# LSWM_00_HCMS29_Lithium.net
KiCad netlist of a schematic drawn in Altium Designer
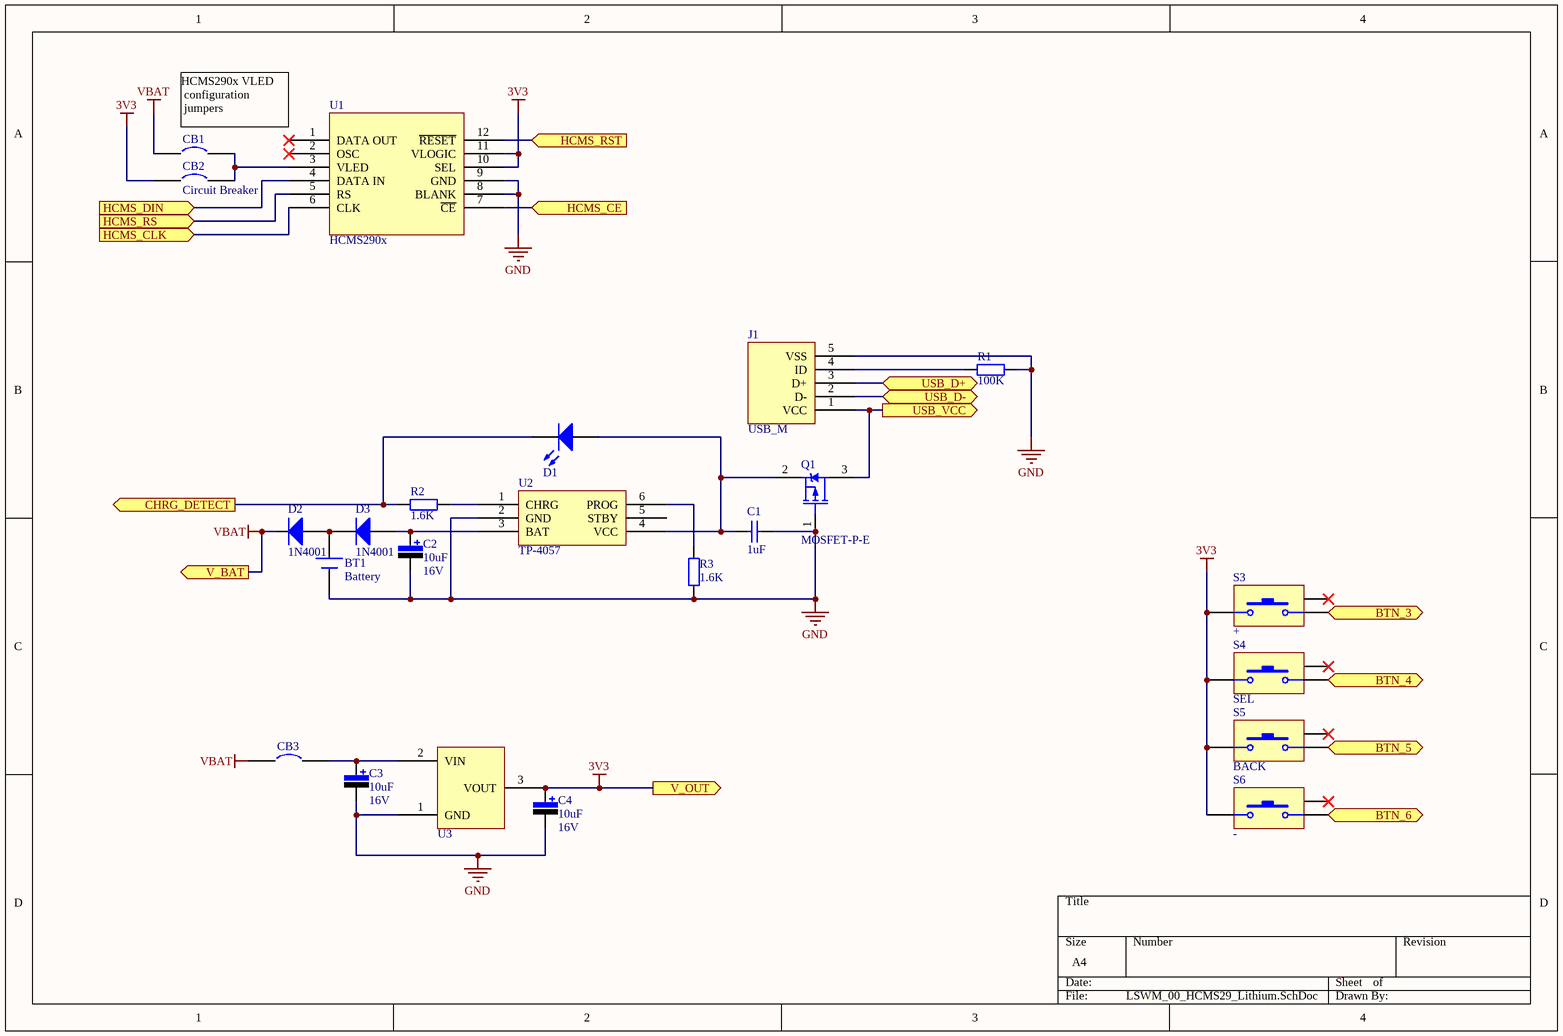
[diagram p0: LSWM_00_HCMS29_Lithium.SchDoc]

(export (version "E")
  (design (tool "Eeschema 10.0.6"))
  (components
    (comp (ref "BT1")
      (value "Battery")
      (footprint "HDR2X1_A")
      (description "备份电池")
      (fields (field (name "PUBLISHER") "Altium Limited"))
      (libsource (lib "Schlib1") (part "Battery_1"))
    )
    (comp (ref "C1")
      (value "1uF")
      (footprint "0805-1")
      (description "无极性电容")
      (fields (field (name "Comment") "Cap") (field (name "PUBLISHER") "Altium Limited"))
      (libsource (lib "fszhang") (part "Cap"))
    )
    (comp (ref "C2")
      (value "10uF")
      (footprint "1206-POL")
      (description "极性电解电容")
      (fields
        (field (name "VOL") "16V")
        (field (name "Comment") "Cap Pol")
        (field (name "PUBLISHER") "Altium Limited")
      )
      (libsource (lib "fszhang") (part "Cap Pol"))
    )
    (comp (ref "C3")
      (value "10uF")
      (footprint "1206-POL")
      (description "极性电解电容")
      (fields
        (field (name "VOL") "16V")
        (field (name "Comment") "Cap Pol")
        (field (name "PUBLISHER") "Altium Limited")
      )
      (libsource (lib "fszhang") (part "Cap Pol"))
    )
    (comp (ref "C4")
      (value "10uF")
      (footprint "1206-POL")
      (description "极性电解电容")
      (fields
        (field (name "VOL") "16V")
        (field (name "Comment") "Cap Pol")
        (field (name "PUBLISHER") "Altium Limited")
      )
      (libsource (lib "fszhang") (part "Cap Pol"))
    )
    (comp (ref "CB1")
      (value "Circuit Breaker")
      (footprint "SB-0805")
      (fields (field (name "PUBLISHER") "Altium Limited"))
      (libsource (lib "Schlib1") (part "Circuit Breaker"))
    )
    (comp (ref "CB2")
      (value "Circuit Breaker")
      (footprint "SB-0805")
      (fields (field (name "PUBLISHER") "Altium Limited"))
      (libsource (lib "Schlib1") (part "Circuit Breaker"))
    )
    (comp (ref "CB3")
      (value "Circuit Breaker")
      (footprint "SB-0805")
      (fields (field (name "PUBLISHER") "Altium Limited"))
      (libsource (lib "Schlib1") (part "Circuit Breaker"))
    )
    (comp (ref "D1")
      (value "LED0")
      (footprint "LED_0805")
      (description "发光二极管")
      (fields (field (name "PUBLISHER") "Altium Limited"))
      (libsource (lib "fszhang") (part "LED0"))
    )
    (comp (ref "D2")
      (value "Diode")
      (footprint "SOD323")
      (description "二极管")
      (fields (field (name "TYPE") "1N4001") (field (name "PUBLISHER") "Altium Limited"))
      (libsource (lib "fszhang") (part "Diode"))
    )
    (comp (ref "D3")
      (value "Diode")
      (footprint "SOD323")
      (description "二极管")
      (fields (field (name "TYPE") "1N4001") (field (name "PUBLISHER") "Altium Limited"))
      (libsource (lib "fszhang") (part "Diode"))
    )
    (comp (ref "J1")
      (value "USB_M")
      (footprint "USB_MICRO")
      (description "MicroUSB接口")
      (libsource (lib "fszhang") (part "USB_M"))
    )
    (comp (ref "Q1")
      (value "MOSFET-P-E")
      (footprint "SOT-23")
      (description "P-Channel Enhanced MOSFET")
      (fields (field (name "PUBLISHER") "Altium Limited"))
      (libsource (lib "Schlib1") (part "MOSFET-P-E"))
    )
    (comp (ref "R1")
      (value "100K")
      (footprint "0603-1")
      (description "贴片电阻")
      (fields (field (name "Comment") "Res1") (field (name "PUBLISHER") "Altium Limited"))
      (libsource (lib "fszhang") (part "Res1"))
    )
    (comp (ref "R2")
      (value "1.6K")
      (footprint "0603-1")
      (description "贴片电阻")
      (fields (field (name "Comment") "Res1") (field (name "PUBLISHER") "Altium Limited"))
      (libsource (lib "") (part "Res1_2"))
    )
    (comp (ref "R3")
      (value "1.6K")
      (footprint "0805-1")
      (description "贴片电阻")
      (fields (field (name "Comment") "Res1") (field (name "PUBLISHER") "Altium Limited"))
      (libsource (lib "") (part "Res1_1"))
    )
    (comp (ref "S3")
      (value "+")
      (footprint "BTN_2_4_35")
      (description "微动开关")
      (fields (field (name "PUBLISHER") "Altium Limited"))
      (libsource (lib "Schlib1") (part "SW-PB"))
    )
    (comp (ref "S4")
      (value "SEL")
      (footprint "BTN_2_4_35")
      (description "微动开关")
      (fields (field (name "PUBLISHER") "Altium Limited"))
      (libsource (lib "Schlib1") (part "SW-PB"))
    )
    (comp (ref "S5")
      (value "BACK")
      (footprint "BTN_2_4_35")
      (description "微动开关")
      (fields (field (name "PUBLISHER") "Altium Limited"))
      (libsource (lib "Schlib1") (part "SW-PB"))
    )
    (comp (ref "S6")
      (value "-")
      (footprint "BTN_2_4_35")
      (description "微动开关")
      (fields (field (name "PUBLISHER") "Altium Limited"))
      (libsource (lib "Schlib1") (part "SW-PB"))
    )
    (comp (ref "U1")
      (value "HCMS290x")
      (footprint "HCMS-290x")
      (description "HCMS LED display module")
      (libsource (lib "Schlib1") (part "HCMS290x"))
    )
    (comp (ref "U2")
      (value "TP-4057")
      (footprint "SOT23-6")
      (description "500mA Linear Lithium Battery Charger")
      (libsource (lib "Schlib1") (part "TP-4057"))
    )
    (comp (ref "U3") (value "HT73xx") (footprint "SOT89N") (libsource (lib "Schlib1") (part "HT73xx")))
  )
  (nets
    (net (code "1") (name "/BTN_3") (class "Default")
      (node (ref "S3") (pin "2") (pinfunction "2_2") (pintype "passive"))
    )
    (net (code "2") (name "/BTN_4") (class "Default")
      (node (ref "S4") (pin "2") (pinfunction "2_2") (pintype "passive"))
    )
    (net (code "3") (name "/BTN_5") (class "Default")
      (node (ref "S5") (pin "2") (pinfunction "2_2") (pintype "passive"))
    )
    (net (code "4") (name "/BTN_6") (class "Default")
      (node (ref "S6") (pin "2") (pinfunction "2_2") (pintype "passive"))
    )
    (net (code "5") (name "/CHRG_DETECT") (class "Default")
      (node (ref "D1") (pin "2") (pinfunction "K_2") (pintype "passive"))
      (node (ref "R2") (pin "2") (pinfunction "2_2") (pintype "passive"))
    )
    (net (code "6") (name "/HCMS_CE") (class "Default")
      (node (ref "U1") (pin "7") (pinfunction "~{CE}_7") (pintype "passive"))
    )
    (net (code "7") (name "/HCMS_CLK") (class "Default")
      (node (ref "U1") (pin "6") (pinfunction "CLK_6") (pintype "passive"))
    )
    (net (code "8") (name "/HCMS_DIN") (class "Default")
      (node (ref "U1") (pin "4") (pinfunction "DATA_IN_4") (pintype "passive"))
    )
    (net (code "9") (name "/HCMS_RS") (class "Default")
      (node (ref "U1") (pin "5") (pinfunction "RS_5") (pintype "passive"))
    )
    (net (code "10") (name "/HCMS_RST") (class "Default")
      (node (ref "U1") (pin "12") (pinfunction "~{RESET}_12") (pintype "passive"))
    )
    (net (code "11") (name "/USB_D+") (class "Default")
      (node (ref "J1") (pin "3") (pinfunction "D+_3") (pintype "passive"))
    )
    (net (code "12") (name "/USB_D-") (class "Default")
      (node (ref "J1") (pin "2") (pinfunction "D-_2") (pintype "passive"))
    )
    (net (code "13") (name "/USB_VCC") (class "Default")
      (node (ref "J1") (pin "1") (pinfunction "VCC_1") (pintype "passive"))
      (node (ref "Q1") (pin "3") (pinfunction "D_3") (pintype "passive"))
    )
    (net (code "14") (name "3V3") (class "Default")
      (node (ref "C4") (pin "1") (pinfunction "1_1") (pintype "passive"))
      (node (ref "CB2") (pin "1") (pinfunction "1_1") (pintype "passive"))
      (node (ref "S3") (pin "1") (pinfunction "1_1") (pintype "passive"))
      (node (ref "S4") (pin "1") (pinfunction "1_1") (pintype "passive"))
      (node (ref "S5") (pin "1") (pinfunction "1_1") (pintype "passive"))
      (node (ref "S6") (pin "1") (pinfunction "1_1") (pintype "passive"))
      (node (ref "U1") (pin "10") (pinfunction "SEL_10") (pintype "passive"))
      (node (ref "U1") (pin "11") (pinfunction "VLOGIC_11") (pintype "passive"))
      (node (ref "U3") (pin "3") (pinfunction "VOUT_3") (pintype "passive"))
    )
    (net (code "15") (name "GND") (class "Default")
      (node (ref "BT1") (pin "2") (pinfunction "-_2") (pintype "passive"))
      (node (ref "C1") (pin "2") (pinfunction "2_2") (pintype "passive"))
      (node (ref "C2") (pin "2") (pinfunction "2_2") (pintype "passive"))
      (node (ref "C3") (pin "2") (pinfunction "2_2") (pintype "passive"))
      (node (ref "C4") (pin "2") (pinfunction "2_2") (pintype "passive"))
      (node (ref "J1") (pin "5") (pinfunction "VSS_5") (pintype "passive"))
      (node (ref "Q1") (pin "1") (pinfunction "G_1") (pintype "passive"))
      (node (ref "R1") (pin "2") (pinfunction "2_2") (pintype "passive"))
      (node (ref "R3") (pin "1") (pinfunction "1_1") (pintype "passive"))
      (node (ref "U1") (pin "8") (pinfunction "BLANK_8") (pintype "passive"))
      (node (ref "U1") (pin "9") (pinfunction "GND_9") (pintype "passive"))
      (node (ref "U2") (pin "2") (pinfunction "GND_2") (pintype "passive"))
      (node (ref "U3") (pin "1") (pinfunction "GND_1") (pintype "passive"))
    )
    (net (code "16") (name "Net-(BT1-+)") (class "Default")
      (node (ref "BT1") (pin "1") (pinfunction "+_1") (pintype "passive"))
      (node (ref "D2") (pin "1") (pinfunction "A_1") (pintype "passive"))
      (node (ref "D3") (pin "2") (pinfunction "K_2") (pintype "passive"))
    )
    (net (code "17") (name "Net-(D1-A)") (class "Default")
      (node (ref "C1") (pin "1") (pinfunction "1_1") (pintype "passive"))
      (node (ref "D1") (pin "1") (pinfunction "A_1") (pintype "passive"))
      (node (ref "Q1") (pin "2") (pinfunction "S_2") (pintype "passive"))
      (node (ref "U2") (pin "4") (pinfunction "VCC_4") (pintype "passive"))
    )
    (net (code "18") (name "Net-(D3-A)") (class "Default")
      (node (ref "C2") (pin "1") (pinfunction "1_1") (pintype "passive"))
      (node (ref "D3") (pin "1") (pinfunction "A_1") (pintype "passive"))
      (node (ref "U2") (pin "3") (pinfunction "BAT_3") (pintype "passive"))
    )
    (net (code "19") (name "Net-(J1-ID)") (class "Default")
      (node (ref "J1") (pin "4") (pinfunction "ID_4") (pintype "passive"))
      (node (ref "R1") (pin "1") (pinfunction "1_1") (pintype "passive"))
    )
    (net (code "20") (name "Net-(U1-VLED)") (class "Default")
      (node (ref "CB1") (pin "2") (pinfunction "2_2") (pintype "passive"))
      (node (ref "CB2") (pin "2") (pinfunction "2_2") (pintype "passive"))
      (node (ref "U1") (pin "3") (pinfunction "VLED_3") (pintype "passive"))
    )
    (net (code "21") (name "Net-(U2-CHRG)") (class "Default")
      (node (ref "R2") (pin "1") (pinfunction "1_1") (pintype "passive"))
      (node (ref "U2") (pin "1") (pinfunction "CHRG_1") (pintype "passive"))
    )
    (net (code "22") (name "Net-(U2-PROG)") (class "Default")
      (node (ref "R3") (pin "2") (pinfunction "2_2") (pintype "passive"))
      (node (ref "U2") (pin "6") (pinfunction "PROG_6") (pintype "passive"))
    )
    (net (code "23") (name "Net-(U3-VIN)") (class "Default")
      (node (ref "C3") (pin "1") (pinfunction "1_1") (pintype "passive"))
      (node (ref "CB3") (pin "2") (pinfunction "2_2") (pintype "passive"))
      (node (ref "U3") (pin "2") (pinfunction "VIN_2") (pintype "passive"))
    )
    (net (code "24") (name "VBAT") (class "Default")
      (node (ref "CB1") (pin "1") (pinfunction "1_1") (pintype "passive"))
      (node (ref "CB3") (pin "1") (pinfunction "1_1") (pintype "passive"))
      (node (ref "D2") (pin "2") (pinfunction "K_2") (pintype "passive"))
    )
    (net (code "25") (name "unconnected-(S3-Pad3)") (class "Default")
      (node (ref "S3") (pin "3") (pinfunction "3_3") (pintype "passive+no_connect"))
    )
    (net (code "26") (name "unconnected-(S4-Pad3)") (class "Default")
      (node (ref "S4") (pin "3") (pinfunction "3_3") (pintype "passive+no_connect"))
    )
    (net (code "27") (name "unconnected-(S5-Pad3)") (class "Default")
      (node (ref "S5") (pin "3") (pinfunction "3_3") (pintype "passive+no_connect"))
    )
    (net (code "28") (name "unconnected-(S6-Pad3)") (class "Default")
      (node (ref "S6") (pin "3") (pinfunction "3_3") (pintype "passive+no_connect"))
    )
    (net (code "29") (name "unconnected-(U1-DATA_OUT-Pad1)") (class "Default")
      (node (ref "U1") (pin "1") (pinfunction "DATA_OUT_1") (pintype "passive+no_connect"))
    )
    (net (code "30") (name "unconnected-(U1-OSC-Pad2)") (class "Default")
      (node (ref "U1") (pin "2") (pinfunction "OSC_2") (pintype "passive+no_connect"))
    )
    (net (code "31") (name "unconnected-(U2-STBY-Pad5)") (class "Default")
      (node (ref "U2") (pin "5") (pinfunction "STBY_5") (pintype "passive"))
    )
  )
)
